# 01-Antennas.net
KiCad netlist of a schematic drawn in Altium Designer
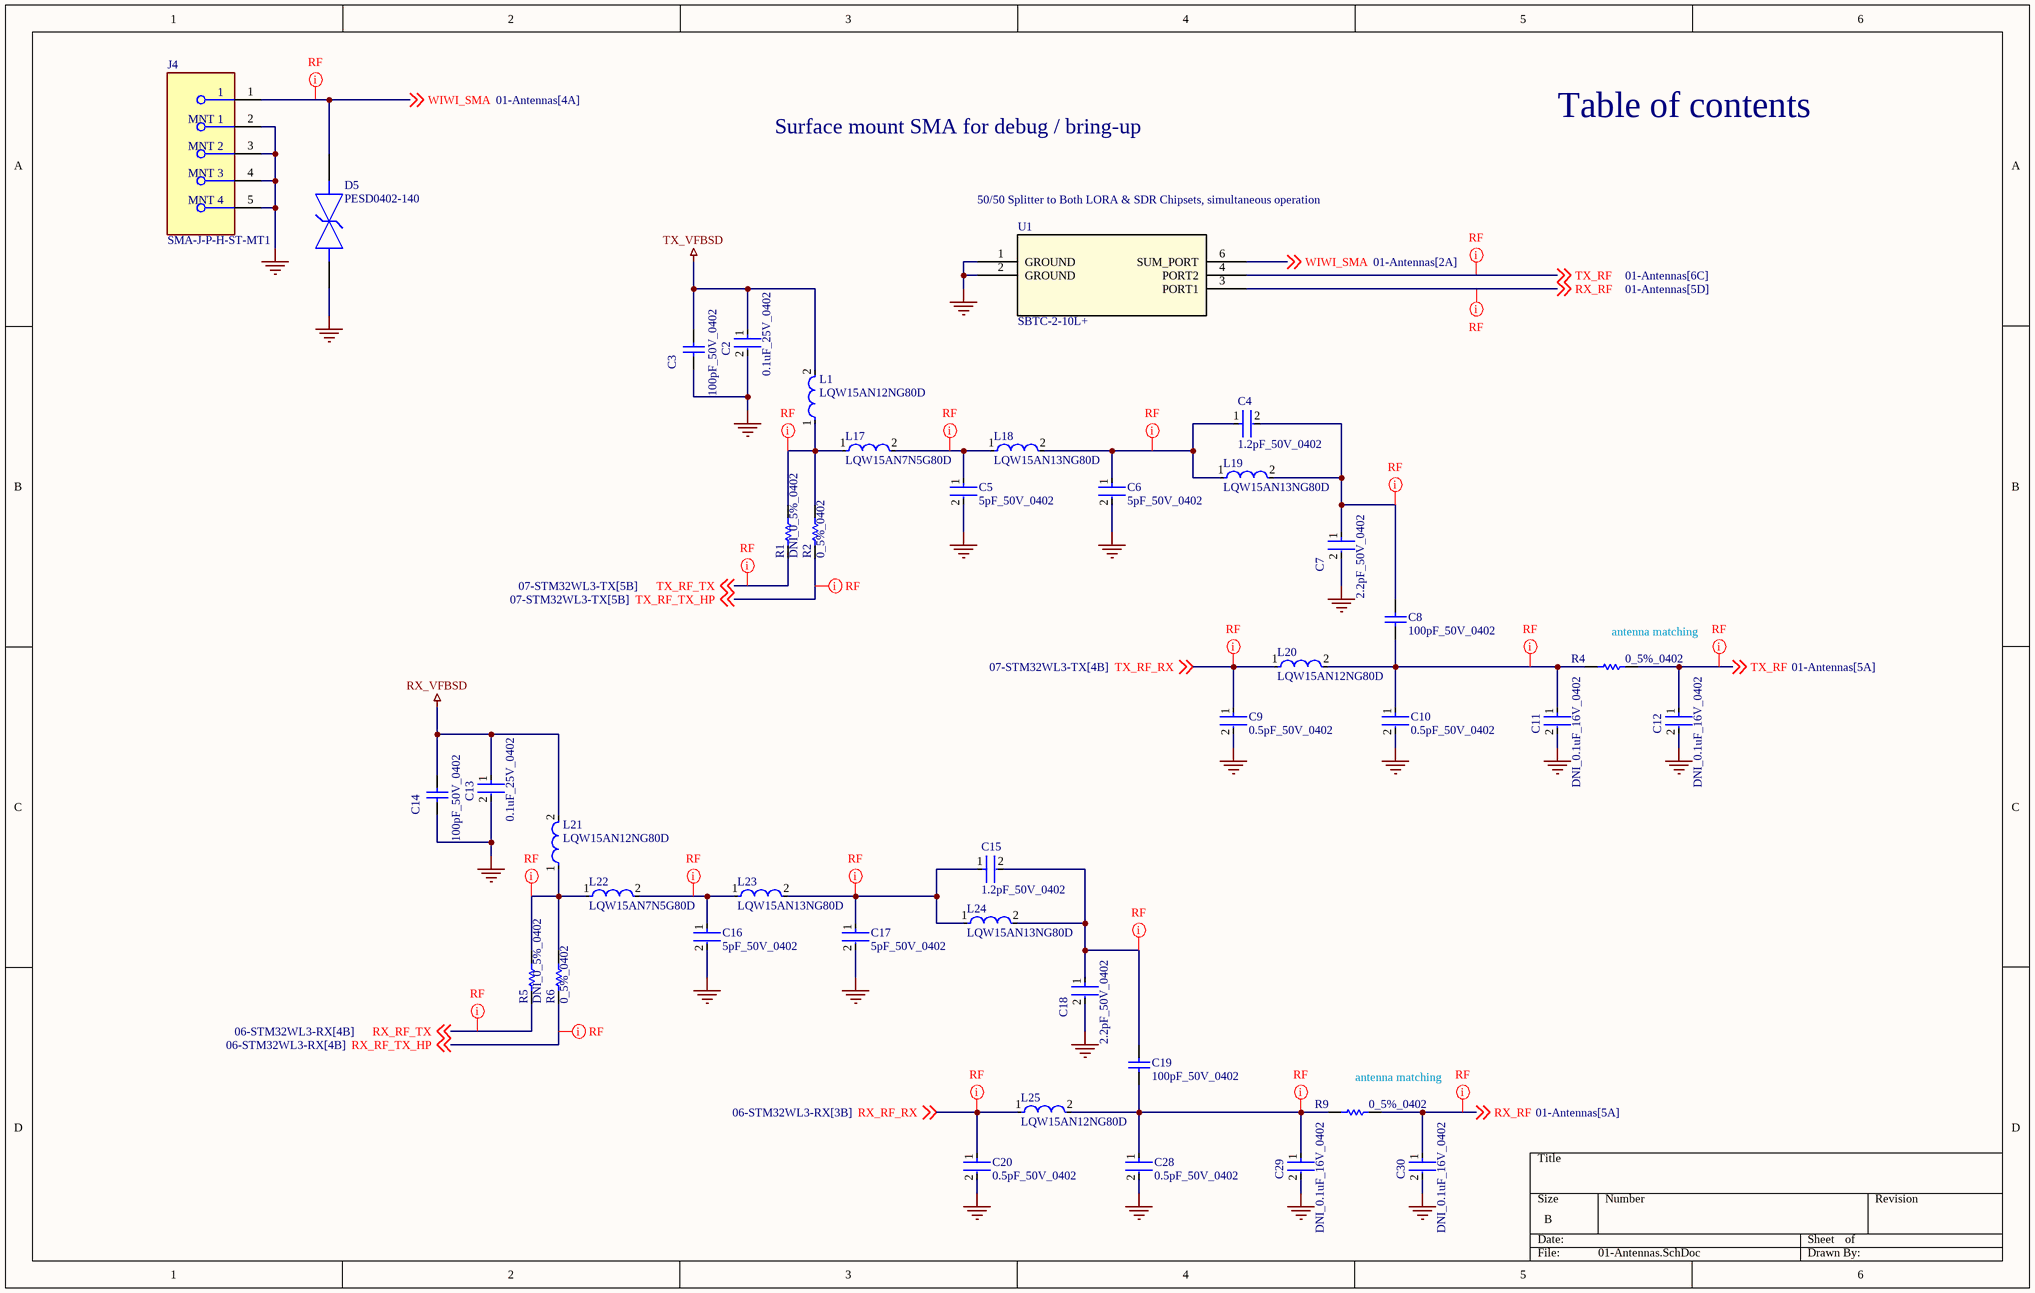
[diagram p0: 01-Antennas.SchDoc]

(export (version "E")
  (design (tool "Eeschema 10.0.6"))
  (components
    (comp (ref "C2")
      (value "0.1uF_25V_0402")
      (footprint "FP-0402-L_1_0_1-W_0_5_0_1-IPC_C")
      (description "General Purpose Ceramic Capacitor, 0402, 100nF, 10%, X7R, 15%, 25V")
      (fields (field (name "VOLTAGE") "25V") (field (name "TOLERANCE") "10%"))
      (libsource (lib "Altium Content Vault") (part "b4654b650e69147ec39a6b967a45e02"))
    )
    (comp (ref "C3")
      (value "100pF_50V_0402")
      (footprint "CAPC1005X55X25ML05T10")
      (fields (field (name "MANUFACTURER") "Murata") (field (name "PART NUMBER") "GRM1555C1H101JA01D"))
      (libsource (lib "Altium Content Vault") (part "CAP"))
    )
    (comp (ref "C4")
      (value "1.2pF_50V_0402")
      (footprint "FP-GJM155-0_05-IPC_A")
      (description "Multi-Layer Ceramic Capacitor 1.2pF C0G  ±0.05pF 0402 Paper T/R")
      (fields (field (name "VOLTAGE") "50V"))
      (libsource (lib "Altium Content Vault") (part "02cd4be3c70576c341d710602a673aa"))
    )
    (comp (ref "C5")
      (value "5pF_50V_0402")
      (footprint "FP-GJM155-0_05-IPC_B")
      (description "Multi-Layer Ceramic Capacitor 5pF C0G  ±0.05pF 0402 Paper T/R")
      (libsource (lib "Altium Content Vault") (part "02cd4be3c70576c341d710602a673aa"))
    )
    (comp (ref "C6")
      (value "5pF_50V_0402")
      (footprint "FP-GJM155-0_05-IPC_B")
      (description "Multi-Layer Ceramic Capacitor 5pF C0G  ±0.05pF 0402 Paper T/R")
      (libsource (lib "Altium Content Vault") (part "02cd4be3c70576c341d710602a673aa"))
    )
    (comp (ref "C7")
      (value "2.2pF_50V_0402")
      (footprint "FP-GJM155-0_05-IPC_C")
      (description "Multi-Layer Ceramic Capacitor 2.2pF C0G  ±0.05pF 0402 Paper T/R")
      (libsource (lib "Altium Content Vault") (part "02cd4be3c70576c341d710602a673aa"))
    )
    (comp (ref "C8")
      (value "100pF_50V_0402")
      (footprint "CAPC1005X55X25ML05T10")
      (fields (field (name "MANUFACTURER") "Murata") (field (name "PART NUMBER") "GRM1555C1H101JA01D"))
      (libsource (lib "Altium Content Vault") (part "CAP"))
    )
    (comp (ref "C9")
      (value "0.5pF_50V_0402")
      (footprint "FP-GJM155-0_05-MFG")
      (description "Multi-Layer Ceramic Capacitor 0.5pF C0G  ±0.1pF 0402 Paper T/R")
      (fields (field (name "VOLTAGE") "50V"))
      (libsource (lib "Altium Content Vault") (part "02cd4be3c70576c341d710602a673aa"))
    )
    (comp (ref "C10")
      (value "0.5pF_50V_0402")
      (footprint "FP-GJM155-0_05-MFG")
      (description "Multi-Layer Ceramic Capacitor 0.5pF C0G  ±0.1pF 0402 Paper T/R")
      (fields (field (name "VOLTAGE") "50V"))
      (libsource (lib "Altium Content Vault") (part "02cd4be3c70576c341d710602a673aa"))
    )
    (comp (ref "C11")
      (value "DNI_0.1uF_16V_0402")
      (footprint "FP-C0402-BB-MFG")
      (description "CAP CER 0.1UF 16V 5% X7R 0402")
      (fields
        (field (name "MANUFACTURER") "Kemet")
        (field (name "MANUFACTURER PART NUMBER") "C0402C104J4RACTU")
      )
      (libsource (lib "Altium Content Vault") (part "b4654b650e69147ec39a6b967a45e02"))
    )
    (comp (ref "C12")
      (value "DNI_0.1uF_16V_0402")
      (footprint "FP-C0402-BB-MFG")
      (description "CAP CER 0.1UF 16V 5% X7R 0402")
      (fields
        (field (name "MANUFACTURER") "Kemet")
        (field (name "MANUFACTURER PART NUMBER") "C0402C104J4RACTU")
      )
      (libsource (lib "Altium Content Vault") (part "b4654b650e69147ec39a6b967a45e02"))
    )
    (comp (ref "C13")
      (value "0.1uF_25V_0402")
      (footprint "FP-0402-L_1_0_1-W_0_5_0_1-IPC_C")
      (description "General Purpose Ceramic Capacitor, 0402, 100nF, 10%, X7R, 15%, 25V")
      (fields (field (name "VOLTAGE") "25V") (field (name "TOLERANCE") "10%"))
      (libsource (lib "Altium Content Vault") (part "b4654b650e69147ec39a6b967a45e02"))
    )
    (comp (ref "C14")
      (value "100pF_50V_0402")
      (footprint "CAPC1005X55X25ML05T10")
      (fields (field (name "MANUFACTURER") "Murata") (field (name "PART NUMBER") "GRM1555C1H101JA01D"))
      (libsource (lib "Altium Content Vault") (part "CAP"))
    )
    (comp (ref "C15")
      (value "1.2pF_50V_0402")
      (footprint "FP-GJM155-0_05-IPC_A")
      (description "Multi-Layer Ceramic Capacitor 1.2pF C0G  ±0.05pF 0402 Paper T/R")
      (fields (field (name "VOLTAGE") "50V"))
      (libsource (lib "Altium Content Vault") (part "02cd4be3c70576c341d710602a673aa"))
    )
    (comp (ref "C16")
      (value "5pF_50V_0402")
      (footprint "FP-GJM155-0_05-IPC_B")
      (description "Multi-Layer Ceramic Capacitor 5pF C0G  ±0.05pF 0402 Paper T/R")
      (libsource (lib "Altium Content Vault") (part "02cd4be3c70576c341d710602a673aa"))
    )
    (comp (ref "C17")
      (value "5pF_50V_0402")
      (footprint "FP-GJM155-0_05-IPC_B")
      (description "Multi-Layer Ceramic Capacitor 5pF C0G  ±0.05pF 0402 Paper T/R")
      (libsource (lib "Altium Content Vault") (part "02cd4be3c70576c341d710602a673aa"))
    )
    (comp (ref "C18")
      (value "2.2pF_50V_0402")
      (footprint "FP-GJM155-0_05-IPC_C")
      (description "Multi-Layer Ceramic Capacitor 2.2pF C0G  ±0.05pF 0402 Paper T/R")
      (libsource (lib "Altium Content Vault") (part "02cd4be3c70576c341d710602a673aa"))
    )
    (comp (ref "C19")
      (value "100pF_50V_0402")
      (footprint "CAPC1005X55X25ML05T10")
      (fields (field (name "MANUFACTURER") "Murata") (field (name "PART NUMBER") "GRM1555C1H101JA01D"))
      (libsource (lib "Altium Content Vault") (part "CAP"))
    )
    (comp (ref "C20")
      (value "0.5pF_50V_0402")
      (footprint "FP-GJM155-0_05-MFG")
      (description "Multi-Layer Ceramic Capacitor 0.5pF C0G  ±0.1pF 0402 Paper T/R")
      (fields (field (name "VOLTAGE") "50V"))
      (libsource (lib "Altium Content Vault") (part "02cd4be3c70576c341d710602a673aa"))
    )
    (comp (ref "C28")
      (value "0.5pF_50V_0402")
      (footprint "FP-GJM155-0_05-MFG")
      (description "Multi-Layer Ceramic Capacitor 0.5pF C0G  ±0.1pF 0402 Paper T/R")
      (fields (field (name "VOLTAGE") "50V"))
      (libsource (lib "Altium Content Vault") (part "02cd4be3c70576c341d710602a673aa"))
    )
    (comp (ref "C29")
      (value "DNI_0.1uF_16V_0402")
      (footprint "FP-C0402-BB-MFG")
      (description "CAP CER 0.1UF 16V 5% X7R 0402")
      (fields
        (field (name "MANUFACTURER") "Kemet")
        (field (name "MANUFACTURER PART NUMBER") "C0402C104J4RACTU")
      )
      (libsource (lib "Altium Content Vault") (part "b4654b650e69147ec39a6b967a45e02"))
    )
    (comp (ref "C30")
      (value "DNI_0.1uF_16V_0402")
      (footprint "FP-C0402-BB-MFG")
      (description "CAP CER 0.1UF 16V 5% X7R 0402")
      (fields
        (field (name "MANUFACTURER") "Kemet")
        (field (name "MANUFACTURER PART NUMBER") "C0402C104J4RACTU")
      )
      (libsource (lib "Altium Content Vault") (part "b4654b650e69147ec39a6b967a45e02"))
    )
    (comp (ref "D5")
      (value "PESD0402-140")
      (footprint "FP-PESD0402-MFG")
      (description "TVS DIODE 14V 40V 0402")
      (fields
        (field (name "OCTOPART") "https://octopart.com/pesd0402-140-littelfuse-74215061")
        (field (name "MANUFACTURER") "Littelfuse Inc.")
      )
      (libsource (lib "Altium Content Vault") (part "edccc070dd5cba1f9372128faf3915e"))
    )
    (comp (ref "J4")
      (value "SMA-J-P-H-ST-MT1")
      (footprint "FP-SMA-J-P-H-ST-MT1-MFG")
      (description "CONN SMA JACK STR 50 OHM SMD")
      (libsource (lib "Altium Content Vault") (part "9c40ac4d87bbbe9fcb330bd20f98ca3"))
    )
    (comp (ref "L1")
      (value "LQW15AN12NG80D")
      (footprint "FP-LQW15AN_80-MFG")
      (description "Wire Wound RF Inductor 12nH ±2% 1240mA 0.093Ω 0402 (1005)")
      (fields (field (name "TOLERANCE") "2%"))
      (libsource (lib "Altium Content Vault") (part "725321dda6339637d4d059423bc1c3c"))
    )
    (comp (ref "L17")
      (value "LQW15AN7N5G80D")
      (footprint "FP-LQW15AN_80-MFG")
      (description "Wire Wound RF Inductor 7.5nH ±2% 1700mA 0.05Ω 0402 (1005)")
      (fields (field (name "TOLERANCE") "2%"))
      (libsource (lib "Altium Content Vault") (part "725321dda6339637d4d059423bc1c3c"))
    )
    (comp (ref "L18")
      (value "LQW15AN13NG80D")
      (footprint "FP-LQW15AN_80-MFG")
      (description "Wire Wound RF Inductor 13nH ±2% 1240mA 0.093Ω 0402 (1005)")
      (fields (field (name "TOLERANCE") "2%"))
      (libsource (lib "Altium Content Vault") (part "725321dda6339637d4d059423bc1c3c"))
    )
    (comp (ref "L19")
      (value "LQW15AN13NG80D")
      (footprint "FP-LQW15AN_80-MFG")
      (description "Wire Wound RF Inductor 13nH ±2% 1240mA 0.093Ω 0402 (1005)")
      (fields (field (name "TOLERANCE") "2%"))
      (libsource (lib "Altium Content Vault") (part "725321dda6339637d4d059423bc1c3c"))
    )
    (comp (ref "L20")
      (value "LQW15AN12NG80D")
      (footprint "FP-LQW15AN_80-MFG")
      (description "Wire Wound RF Inductor 12nH ±2% 1240mA 0.093Ω 0402 (1005)")
      (fields (field (name "TOLERANCE") "2%"))
      (libsource (lib "Altium Content Vault") (part "725321dda6339637d4d059423bc1c3c"))
    )
    (comp (ref "L21")
      (value "LQW15AN12NG80D")
      (footprint "FP-LQW15AN_80-MFG")
      (description "Wire Wound RF Inductor 12nH ±2% 1240mA 0.093Ω 0402 (1005)")
      (fields (field (name "TOLERANCE") "2%"))
      (libsource (lib "Altium Content Vault") (part "725321dda6339637d4d059423bc1c3c"))
    )
    (comp (ref "L22")
      (value "LQW15AN7N5G80D")
      (footprint "FP-LQW15AN_80-MFG")
      (description "Wire Wound RF Inductor 7.5nH ±2% 1700mA 0.05Ω 0402 (1005)")
      (fields (field (name "TOLERANCE") "2%"))
      (libsource (lib "Altium Content Vault") (part "725321dda6339637d4d059423bc1c3c"))
    )
    (comp (ref "L23")
      (value "LQW15AN13NG80D")
      (footprint "FP-LQW15AN_80-MFG")
      (description "Wire Wound RF Inductor 13nH ±2% 1240mA 0.093Ω 0402 (1005)")
      (fields (field (name "TOLERANCE") "2%"))
      (libsource (lib "Altium Content Vault") (part "725321dda6339637d4d059423bc1c3c"))
    )
    (comp (ref "L24")
      (value "LQW15AN13NG80D")
      (footprint "FP-LQW15AN_80-MFG")
      (description "Wire Wound RF Inductor 13nH ±2% 1240mA 0.093Ω 0402 (1005)")
      (fields (field (name "TOLERANCE") "2%"))
      (libsource (lib "Altium Content Vault") (part "725321dda6339637d4d059423bc1c3c"))
    )
    (comp (ref "L25")
      (value "LQW15AN12NG80D")
      (footprint "FP-LQW15AN_80-MFG")
      (description "Wire Wound RF Inductor 12nH ±2% 1240mA 0.093Ω 0402 (1005)")
      (fields (field (name "TOLERANCE") "2%"))
      (libsource (lib "Altium Content Vault") (part "725321dda6339637d4d059423bc1c3c"))
    )
    (comp (ref "R1")
      (value "DNI_0_5%_0402")
      (footprint "RESC1005X40X25NL05T10")
      (fields (field (name "MANUFACTURER") "Panasonic") (field (name "PART NUMBER") "ERJ-U020R00X"))
      (libsource (lib "Altium Content Vault") (part "RES"))
    )
    (comp (ref "R2")
      (value "0_5%_0402")
      (footprint "RESC1005X40X25NL05T10")
      (fields (field (name "MANUFACTURER") "Panasonic") (field (name "PART NUMBER") "ERJ-U020R00X"))
      (libsource (lib "Altium Content Vault") (part "RES"))
    )
    (comp (ref "R4")
      (value "0_5%_0402")
      (footprint "RESC1005X40X25NL05T10")
      (fields (field (name "MANUFACTURER") "Panasonic") (field (name "PART NUMBER") "ERJ-U020R00X"))
      (libsource (lib "Altium Content Vault") (part "RES"))
    )
    (comp (ref "R5")
      (value "DNI_0_5%_0402")
      (footprint "RESC1005X40X25NL05T10")
      (fields (field (name "MANUFACTURER") "Panasonic") (field (name "PART NUMBER") "ERJ-U020R00X"))
      (libsource (lib "Altium Content Vault") (part "RES"))
    )
    (comp (ref "R6")
      (value "0_5%_0402")
      (footprint "RESC1005X40X25NL05T10")
      (fields (field (name "MANUFACTURER") "Panasonic") (field (name "PART NUMBER") "ERJ-U020R00X"))
      (libsource (lib "Altium Content Vault") (part "RES"))
    )
    (comp (ref "R9")
      (value "0_5%_0402")
      (footprint "RESC1005X40X25NL05T10")
      (fields (field (name "MANUFACTURER") "Panasonic") (field (name "PART NUMBER") "ERJ-U020R00X"))
      (libsource (lib "Altium Content Vault") (part "RES"))
    )
    (comp (ref "U1")
      (value "SBTC-2-10L+")
      (footprint "AT1029_MNC")
      (description "No Description Available")
      (fields (field (name "COPYRIGHT") "Copyright (C) 2023 Ultra Librarian. All rights reserved."))
      (libsource (lib "SBTC-2-10L&plus_") (part "SBTC-2-10L+"))
    )
  )
  (nets
    (net (code "1") (name "GND") (class "Default")
      (node (ref "C10") (pin "2") (pinfunction "2_2") (pintype "passive"))
      (node (ref "C11") (pin "2") (pinfunction "2_2") (pintype "passive"))
      (node (ref "C12") (pin "2") (pinfunction "2_2") (pintype "passive"))
      (node (ref "C13") (pin "2") (pinfunction "2_2") (pintype "passive"))
      (node (ref "C14") (pin "1") (pinfunction "1_1") (pintype "passive"))
      (node (ref "C16") (pin "2") (pinfunction "2_2") (pintype "passive"))
      (node (ref "C17") (pin "2") (pinfunction "2_2") (pintype "passive"))
      (node (ref "C18") (pin "2") (pinfunction "2_2") (pintype "passive"))
      (node (ref "C2") (pin "2") (pinfunction "2_2") (pintype "passive"))
      (node (ref "C20") (pin "2") (pinfunction "2_2") (pintype "passive"))
      (node (ref "C28") (pin "2") (pinfunction "2_2") (pintype "passive"))
      (node (ref "C29") (pin "2") (pinfunction "2_2") (pintype "passive"))
      (node (ref "C3") (pin "1") (pinfunction "1_1") (pintype "passive"))
      (node (ref "C30") (pin "2") (pinfunction "2_2") (pintype "passive"))
      (node (ref "C5") (pin "2") (pinfunction "2_2") (pintype "passive"))
      (node (ref "C6") (pin "2") (pinfunction "2_2") (pintype "passive"))
      (node (ref "C7") (pin "2") (pinfunction "2_2") (pintype "passive"))
      (node (ref "C9") (pin "2") (pinfunction "2_2") (pintype "passive"))
      (node (ref "D5") (pin "1") (pinfunction "1_1") (pintype "passive"))
      (node (ref "J4") (pin "2") (pinfunction "MNT_1_2") (pintype "passive"))
      (node (ref "J4") (pin "3") (pinfunction "MNT_2_3") (pintype "passive"))
      (node (ref "J4") (pin "4") (pinfunction "MNT_3_4") (pintype "passive"))
      (node (ref "J4") (pin "5") (pinfunction "MNT_4_5") (pintype "passive"))
      (node (ref "U1") (pin "1") (pinfunction "GROUND_1") (pintype "passive"))
      (node (ref "U1") (pin "2") (pinfunction "GROUND_2") (pintype "passive"))
    )
    (net (code "2") (name "Net-(C4-Pad1)") (class "Default")
      (node (ref "C4") (pin "1") (pinfunction "1_1") (pintype "passive"))
      (node (ref "C6") (pin "1") (pinfunction "1_1") (pintype "passive"))
      (node (ref "L18") (pin "2") (pinfunction "2_2") (pintype "passive"))
      (node (ref "L19") (pin "1") (pinfunction "1_1") (pintype "passive"))
    )
    (net (code "3") (name "Net-(C4-Pad2)") (class "Default")
      (node (ref "C4") (pin "2") (pinfunction "2_2") (pintype "passive"))
      (node (ref "C7") (pin "1") (pinfunction "1_1") (pintype "passive"))
      (node (ref "C8") (pin "2") (pinfunction "2_2") (pintype "passive"))
      (node (ref "L19") (pin "2") (pinfunction "2_2") (pintype "passive"))
    )
    (net (code "4") (name "Net-(C5-Pad1)") (class "Default")
      (node (ref "C5") (pin "1") (pinfunction "1_1") (pintype "passive"))
      (node (ref "L17") (pin "2") (pinfunction "2_2") (pintype "passive"))
      (node (ref "L18") (pin "1") (pinfunction "1_1") (pintype "passive"))
    )
    (net (code "5") (name "Net-(C10-Pad1)") (class "Default")
      (node (ref "C10") (pin "1") (pinfunction "1_1") (pintype "passive"))
      (node (ref "C11") (pin "1") (pinfunction "1_1") (pintype "passive"))
      (node (ref "C8") (pin "1") (pinfunction "1_1") (pintype "passive"))
      (node (ref "L20") (pin "2") (pinfunction "2_2") (pintype "passive"))
      (node (ref "R4") (pin "1") (pinfunction "1_1") (pintype "passive"))
    )
    (net (code "6") (name "Net-(C15-Pad1)") (class "Default")
      (node (ref "C15") (pin "1") (pinfunction "1_1") (pintype "passive"))
      (node (ref "C17") (pin "1") (pinfunction "1_1") (pintype "passive"))
      (node (ref "L23") (pin "2") (pinfunction "2_2") (pintype "passive"))
      (node (ref "L24") (pin "1") (pinfunction "1_1") (pintype "passive"))
    )
    (net (code "7") (name "Net-(C15-Pad2)") (class "Default")
      (node (ref "C15") (pin "2") (pinfunction "2_2") (pintype "passive"))
      (node (ref "C18") (pin "1") (pinfunction "1_1") (pintype "passive"))
      (node (ref "C19") (pin "2") (pinfunction "2_2") (pintype "passive"))
      (node (ref "L24") (pin "2") (pinfunction "2_2") (pintype "passive"))
    )
    (net (code "8") (name "Net-(C16-Pad1)") (class "Default")
      (node (ref "C16") (pin "1") (pinfunction "1_1") (pintype "passive"))
      (node (ref "L22") (pin "2") (pinfunction "2_2") (pintype "passive"))
      (node (ref "L23") (pin "1") (pinfunction "1_1") (pintype "passive"))
    )
    (net (code "9") (name "Net-(C19-Pad1)") (class "Default")
      (node (ref "C19") (pin "1") (pinfunction "1_1") (pintype "passive"))
      (node (ref "C28") (pin "1") (pinfunction "1_1") (pintype "passive"))
      (node (ref "C29") (pin "1") (pinfunction "1_1") (pintype "passive"))
      (node (ref "L25") (pin "2") (pinfunction "2_2") (pintype "passive"))
      (node (ref "R9") (pin "1") (pinfunction "1_1") (pintype "passive"))
    )
    (net (code "10") (name "Net-(L1-Pad1)") (class "Default")
      (node (ref "L1") (pin "1") (pinfunction "1_1") (pintype "passive"))
      (node (ref "L17") (pin "1") (pinfunction "1_1") (pintype "passive"))
      (node (ref "R1") (pin "2") (pinfunction "2_2") (pintype "passive"))
      (node (ref "R2") (pin "2") (pinfunction "2_2") (pintype "passive"))
    )
    (net (code "11") (name "Net-(L21-Pad1)") (class "Default")
      (node (ref "L21") (pin "1") (pinfunction "1_1") (pintype "passive"))
      (node (ref "L22") (pin "1") (pinfunction "1_1") (pintype "passive"))
      (node (ref "R5") (pin "2") (pinfunction "2_2") (pintype "passive"))
      (node (ref "R6") (pin "2") (pinfunction "2_2") (pintype "passive"))
    )
    (net (code "12") (name "RX_RF") (class "Default")
      (node (ref "C30") (pin "1") (pinfunction "1_1") (pintype "passive"))
      (node (ref "R9") (pin "2") (pinfunction "2_2") (pintype "passive"))
      (node (ref "U1") (pin "3") (pinfunction "PORT1_3") (pintype "passive"))
    )
    (net (code "13") (name "RX_RF_RX") (class "Default")
      (node (ref "C20") (pin "1") (pinfunction "1_1") (pintype "passive"))
      (node (ref "L25") (pin "1") (pinfunction "1_1") (pintype "passive"))
    )
    (net (code "14") (name "RX_RF_TX") (class "Default")
      (node (ref "R5") (pin "1") (pinfunction "1_1") (pintype "passive"))
    )
    (net (code "15") (name "RX_RF_TX_HP") (class "Default")
      (node (ref "R6") (pin "1") (pinfunction "1_1") (pintype "passive"))
    )
    (net (code "16") (name "RX_VFBSD") (class "Default")
      (node (ref "C13") (pin "1") (pinfunction "1_1") (pintype "passive"))
      (node (ref "C14") (pin "2") (pinfunction "2_2") (pintype "passive"))
      (node (ref "L21") (pin "2") (pinfunction "2_2") (pintype "passive"))
    )
    (net (code "17") (name "TX_RF") (class "Default")
      (node (ref "C12") (pin "1") (pinfunction "1_1") (pintype "passive"))
      (node (ref "R4") (pin "2") (pinfunction "2_2") (pintype "passive"))
      (node (ref "U1") (pin "4") (pinfunction "PORT2_4") (pintype "passive"))
    )
    (net (code "18") (name "TX_RF_RX") (class "Default")
      (node (ref "C9") (pin "1") (pinfunction "1_1") (pintype "passive"))
      (node (ref "L20") (pin "1") (pinfunction "1_1") (pintype "passive"))
    )
    (net (code "19") (name "TX_RF_TX") (class "Default")
      (node (ref "R1") (pin "1") (pinfunction "1_1") (pintype "passive"))
    )
    (net (code "20") (name "TX_RF_TX_HP") (class "Default")
      (node (ref "R2") (pin "1") (pinfunction "1_1") (pintype "passive"))
    )
    (net (code "21") (name "TX_VFBSD") (class "Default")
      (node (ref "C2") (pin "1") (pinfunction "1_1") (pintype "passive"))
      (node (ref "C3") (pin "2") (pinfunction "2_2") (pintype "passive"))
      (node (ref "L1") (pin "2") (pinfunction "2_2") (pintype "passive"))
    )
    (net (code "22") (name "WIWI_SMA") (class "Default")
      (node (ref "D5") (pin "2") (pinfunction "2_2") (pintype "passive"))
      (node (ref "J4") (pin "1") (pinfunction "1_1") (pintype "passive"))
      (node (ref "U1") (pin "6") (pinfunction "SUM_PORT_6") (pintype "passive"))
    )
  )
)
